# module_RevB.net
KiCad netlist of a schematic drawn in EAGLE
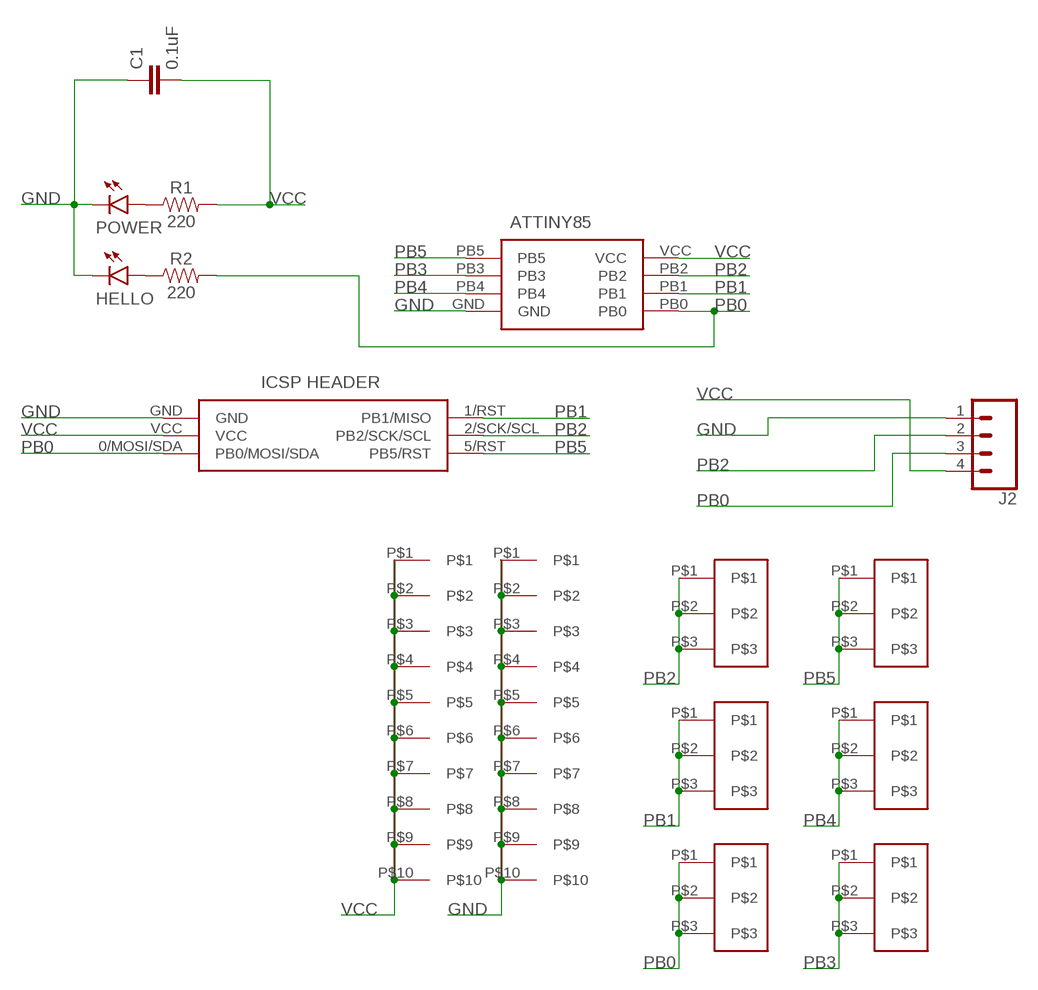
[diagram p0: schematic, sheet 1]

(export (version "E")
  (design (tool "Eeschema 10.0.6"))
  (components
    (comp (ref "0")
      (value "3X-PADS-CONNECTED")
      (footprint "eagle-import:3X-PADS")
      (libsource (lib "eagle-import") (part "3X-PADS-CONNECTED"))
    )
    (comp (ref "1")
      (value "3X-PADS-CONNECTED")
      (footprint "eagle-import:3X-PADS")
      (libsource (lib "eagle-import") (part "3X-PADS-CONNECTED"))
    )
    (comp (ref "2")
      (value "3X-PADS-CONNECTED")
      (footprint "eagle-import:3X-PADS")
      (libsource (lib "eagle-import") (part "3X-PADS-CONNECTED"))
    )
    (comp (ref "3")
      (value "3X-PADS-CONNECTED")
      (footprint "eagle-import:3X-PADS")
      (libsource (lib "eagle-import") (part "3X-PADS-CONNECTED"))
    )
    (comp (ref "4")
      (value "3X-PADS-CONNECTED")
      (footprint "eagle-import:3X-PADS")
      (libsource (lib "eagle-import") (part "3X-PADS-CONNECTED"))
    )
    (comp (ref "5")
      (value "3X-PADS-CONNECTED")
      (footprint "eagle-import:3X-PADS")
      (libsource (lib "eagle-import") (part "3X-PADS-CONNECTED"))
    )
    (comp (ref "C1")
      (value "0.1uF")
      (footprint "eagle-import:0603")
      (libsource (lib "eagle-import") (part "0.1UF-0603-25V-5%"))
    )
    (comp (ref "GND")
      (value "10X-PADS")
      (footprint "eagle-import:10X-PADS")
      (libsource (lib "eagle-import") (part "10X-PADS"))
    )
    (comp (ref "HELLO")
      (value "LED3MM")
      (footprint "eagle-import:LED3MM")
      (libsource (lib "eagle-import") (part "LED3MM"))
    )
    (comp (ref "IC1")
      (value "ATTINY85-20SU")
      (footprint "eagle-import:SOT127P798X216-8N")
      (fields (field (name "RS_PART_NUMBER") "1331674"))
      (libsource (lib "eagle-import") (part "ATTINY85-20SU"))
    )
    (comp (ref "J1")
      (value "M20-9980346")
      (footprint "eagle-import:HDRV6W64P254_2X3_762X508X868P")
      (fields (field (name "RS_PART_NUMBER") "7457046P"))
      (libsource (lib "eagle-import") (part "M20-9980346"))
    )
    (comp (ref "J2")
      (value "CONN_04")
      (footprint "eagle-import:1X04")
      (libsource (lib "eagle-import") (part "CONN_04"))
    )
    (comp (ref "POWER")
      (value "LED3MM")
      (footprint "eagle-import:LED3MM")
      (libsource (lib "eagle-import") (part "LED3MM"))
    )
    (comp (ref "R1")
      (value "220")
      (footprint "eagle-import:AXIAL-0.3")
      (libsource (lib "eagle-import") (part "RESISTORAXIAL-0.3"))
    )
    (comp (ref "R2")
      (value "220")
      (footprint "eagle-import:AXIAL-0.3")
      (libsource (lib "eagle-import") (part "RESISTORAXIAL-0.3"))
    )
    (comp (ref "VCC")
      (value "10X-PADS")
      (footprint "eagle-import:10X-PADS")
      (libsource (lib "eagle-import") (part "10X-PADS"))
    )
  )
  (nets
    (net (code "1") (name "/GND") (class "Default")
      (node (ref "C1") (pin "1") (pinfunction "1_1") (pintype "passive"))
      (node (ref "GND") (pin "P$1") (pinfunction "P$1_P$1") (pintype "bidirectional"))
      (node (ref "GND") (pin "P$10") (pinfunction "P$10_P$10") (pintype "bidirectional"))
      (node (ref "GND") (pin "P$2") (pinfunction "P$2_P$2") (pintype "bidirectional"))
      (node (ref "GND") (pin "P$3") (pinfunction "P$3_P$3") (pintype "bidirectional"))
      (node (ref "GND") (pin "P$4") (pinfunction "P$4_P$4") (pintype "bidirectional"))
      (node (ref "GND") (pin "P$5") (pinfunction "P$5_P$5") (pintype "bidirectional"))
      (node (ref "GND") (pin "P$6") (pinfunction "P$6_P$6") (pintype "bidirectional"))
      (node (ref "GND") (pin "P$7") (pinfunction "P$7_P$7") (pintype "bidirectional"))
      (node (ref "GND") (pin "P$8") (pinfunction "P$8_P$8") (pintype "bidirectional"))
      (node (ref "GND") (pin "P$9") (pinfunction "P$9_P$9") (pintype "bidirectional"))
      (node (ref "HELLO") (pin "NEG") (pinfunction "NEG_NEG") (pintype "passive"))
      (node (ref "IC1") (pin "GND") (pinfunction "GND_GND") (pintype "bidirectional"))
      (node (ref "J1") (pin "GND") (pinfunction "GND_GND") (pintype "bidirectional"))
      (node (ref "J2") (pin "1") (pinfunction "1_1") (pintype "passive"))
      (node (ref "POWER") (pin "NEG") (pinfunction "NEG_NEG") (pintype "passive"))
    )
    (net (code "2") (name "/PB0") (class "Default")
      (node (ref "0") (pin "P$1") (pinfunction "P$1_P$1") (pintype "bidirectional"))
      (node (ref "0") (pin "P$2") (pinfunction "P$2_P$2") (pintype "bidirectional"))
      (node (ref "0") (pin "P$3") (pinfunction "P$3_P$3") (pintype "bidirectional"))
      (node (ref "IC1") (pin "PB0") (pinfunction "PB0_PB0") (pintype "bidirectional"))
      (node (ref "J1") (pin "0/MOSI/SDA") (pinfunction "PB0/MOSI/SDA_0/MOSI/SDA") (pintype "bidirectional"))
      (node (ref "J2") (pin "3") (pinfunction "3_3") (pintype "passive"))
      (node (ref "R2") (pin "P$2") (pinfunction "2_P$2") (pintype "passive"))
    )
    (net (code "3") (name "/PB1") (class "Default")
      (node (ref "1") (pin "P$1") (pinfunction "P$1_P$1") (pintype "bidirectional"))
      (node (ref "1") (pin "P$2") (pinfunction "P$2_P$2") (pintype "bidirectional"))
      (node (ref "1") (pin "P$3") (pinfunction "P$3_P$3") (pintype "bidirectional"))
      (node (ref "IC1") (pin "PB1") (pinfunction "PB1_PB1") (pintype "bidirectional"))
      (node (ref "J1") (pin "1/RST") (pinfunction "PB1/MISO_1/RST") (pintype "bidirectional"))
    )
    (net (code "4") (name "/PB2") (class "Default")
      (node (ref "2") (pin "P$1") (pinfunction "P$1_P$1") (pintype "bidirectional"))
      (node (ref "2") (pin "P$2") (pinfunction "P$2_P$2") (pintype "bidirectional"))
      (node (ref "2") (pin "P$3") (pinfunction "P$3_P$3") (pintype "bidirectional"))
      (node (ref "IC1") (pin "PB2") (pinfunction "PB2_PB2") (pintype "bidirectional"))
      (node (ref "J1") (pin "2/SCK/SCL") (pinfunction "PB2/SCK/SCL_2/SCK/SCL") (pintype "bidirectional"))
      (node (ref "J2") (pin "2") (pinfunction "2_2") (pintype "passive"))
    )
    (net (code "5") (name "/PB3") (class "Default")
      (node (ref "3") (pin "P$1") (pinfunction "P$1_P$1") (pintype "bidirectional"))
      (node (ref "3") (pin "P$2") (pinfunction "P$2_P$2") (pintype "bidirectional"))
      (node (ref "3") (pin "P$3") (pinfunction "P$3_P$3") (pintype "bidirectional"))
      (node (ref "IC1") (pin "PB3") (pinfunction "PB3_PB3") (pintype "bidirectional"))
    )
    (net (code "6") (name "/PB4") (class "Default")
      (node (ref "4") (pin "P$1") (pinfunction "P$1_P$1") (pintype "bidirectional"))
      (node (ref "4") (pin "P$2") (pinfunction "P$2_P$2") (pintype "bidirectional"))
      (node (ref "4") (pin "P$3") (pinfunction "P$3_P$3") (pintype "bidirectional"))
      (node (ref "IC1") (pin "PB4") (pinfunction "PB4_PB4") (pintype "bidirectional"))
    )
    (net (code "7") (name "/PB5") (class "Default")
      (node (ref "5") (pin "P$1") (pinfunction "P$1_P$1") (pintype "bidirectional"))
      (node (ref "5") (pin "P$2") (pinfunction "P$2_P$2") (pintype "bidirectional"))
      (node (ref "5") (pin "P$3") (pinfunction "P$3_P$3") (pintype "bidirectional"))
      (node (ref "IC1") (pin "PB5") (pinfunction "PB5_PB5") (pintype "bidirectional"))
      (node (ref "J1") (pin "5/RST") (pinfunction "PB5/RST_5/RST") (pintype "bidirectional"))
    )
    (net (code "8") (name "/VCC") (class "Default")
      (node (ref "C1") (pin "2") (pinfunction "2_2") (pintype "passive"))
      (node (ref "IC1") (pin "VCC") (pinfunction "VCC_VCC") (pintype "bidirectional"))
      (node (ref "J1") (pin "VCC") (pinfunction "VCC_VCC") (pintype "bidirectional"))
      (node (ref "J2") (pin "4") (pinfunction "4_4") (pintype "passive"))
      (node (ref "R1") (pin "P$2") (pinfunction "2_P$2") (pintype "passive"))
      (node (ref "VCC") (pin "P$1") (pinfunction "P$1_P$1") (pintype "bidirectional"))
      (node (ref "VCC") (pin "P$10") (pinfunction "P$10_P$10") (pintype "bidirectional"))
      (node (ref "VCC") (pin "P$2") (pinfunction "P$2_P$2") (pintype "bidirectional"))
      (node (ref "VCC") (pin "P$3") (pinfunction "P$3_P$3") (pintype "bidirectional"))
      (node (ref "VCC") (pin "P$4") (pinfunction "P$4_P$4") (pintype "bidirectional"))
      (node (ref "VCC") (pin "P$5") (pinfunction "P$5_P$5") (pintype "bidirectional"))
      (node (ref "VCC") (pin "P$6") (pinfunction "P$6_P$6") (pintype "bidirectional"))
      (node (ref "VCC") (pin "P$7") (pinfunction "P$7_P$7") (pintype "bidirectional"))
      (node (ref "VCC") (pin "P$8") (pinfunction "P$8_P$8") (pintype "bidirectional"))
      (node (ref "VCC") (pin "P$9") (pinfunction "P$9_P$9") (pintype "bidirectional"))
    )
    (net (code "9") (name "Net-(R1-1)") (class "Default")
      (node (ref "POWER") (pin "POS") (pinfunction "POS_POS") (pintype "passive"))
      (node (ref "R1") (pin "P$1") (pinfunction "1_P$1") (pintype "passive"))
    )
    (net (code "10") (name "Net-(R2-1)") (class "Default")
      (node (ref "HELLO") (pin "POS") (pinfunction "POS_POS") (pintype "passive"))
      (node (ref "R2") (pin "P$1") (pinfunction "1_P$1") (pintype "passive"))
    )
  )
)
